# Scheme_alt.net
KiCad netlist of a schematic drawn in EAGLE
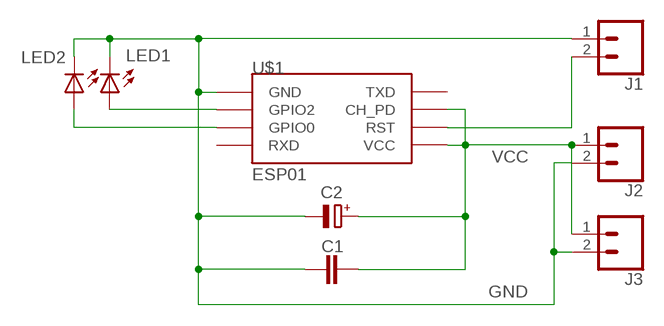
[diagram p0: schematic, sheet 1]

(export (version "E")
  (design (tool "Eeschema 10.0.6"))
  (components
    (comp (ref "C1")
      (value "C-EU025-024X044")
      (footprint "eagle-import:C025-024X044")
      (libsource (lib "eagle-import") (part "C-EU025-024X044"))
    )
    (comp (ref "C2")
      (value "CPOL-EUE5-10.5")
      (footprint "eagle-import:E5-10,5")
      (libsource (lib "eagle-import") (part "CPOL-EUE5-10.5"))
    )
    (comp (ref "J1")
      (value "CONN_02")
      (footprint "eagle-import:1X02")
      (libsource (lib "eagle-import") (part "CONN_02"))
    )
    (comp (ref "J2")
      (value "CONN_02")
      (footprint "eagle-import:1X02")
      (libsource (lib "eagle-import") (part "CONN_02"))
    )
    (comp (ref "J3")
      (value "CONN_02")
      (footprint "eagle-import:1X02")
      (libsource (lib "eagle-import") (part "CONN_02"))
    )
    (comp (ref "LED1")
      (value "LED3MM")
      (footprint "eagle-import:LED3MM")
      (libsource (lib "eagle-import") (part "LED3MM"))
    )
    (comp (ref "LED2")
      (value "LED3MM")
      (footprint "eagle-import:LED3MM")
      (libsource (lib "eagle-import") (part "LED3MM"))
    )
    (comp (ref "U$1")
      (value "ESP01")
      (footprint "eagle-import:ESP01")
      (libsource (lib "eagle-import") (part "ESP01"))
    )
  )
  (nets
    (net (code "1") (name "/GND") (class "Default")
      (node (ref "C1") (pin "2") (pinfunction "2_2") (pintype "passive"))
      (node (ref "C2") (pin "-") (pinfunction "-_-") (pintype "passive"))
      (node (ref "J1") (pin "1") (pinfunction "1_1") (pintype "passive"))
      (node (ref "J2") (pin "2") (pinfunction "2_2") (pintype "passive"))
      (node (ref "J3") (pin "2") (pinfunction "2_2") (pintype "passive"))
      (node (ref "LED1") (pin "K") (pinfunction "C_K") (pintype "passive"))
      (node (ref "LED2") (pin "K") (pinfunction "C_K") (pintype "passive"))
      (node (ref "U$1") (pin "GND") (pinfunction "GND_GND") (pintype "bidirectional"))
    )
    (net (code "2") (name "/VCC") (class "Default")
      (node (ref "C1") (pin "1") (pinfunction "1_1") (pintype "passive"))
      (node (ref "C2") (pin "+") (pinfunction "+_+") (pintype "passive"))
      (node (ref "J2") (pin "1") (pinfunction "1_1") (pintype "passive"))
      (node (ref "J3") (pin "1") (pinfunction "1_1") (pintype "passive"))
      (node (ref "U$1") (pin "CH_PD") (pinfunction "CH_PD_CH_PD") (pintype "bidirectional"))
      (node (ref "U$1") (pin "VCC") (pinfunction "VCC_VCC") (pintype "bidirectional"))
    )
    (net (code "3") (name "Net-(J1-Pad2)") (class "Default")
      (node (ref "J1") (pin "2") (pinfunction "2_2") (pintype "passive"))
      (node (ref "U$1") (pin "RST") (pinfunction "RST_RST") (pintype "bidirectional"))
    )
    (net (code "4") (name "Net-(LED1-PadA)") (class "Default")
      (node (ref "LED1") (pin "A") (pinfunction "A_A") (pintype "passive"))
      (node (ref "U$1") (pin "GPIO2") (pinfunction "GPIO2_GPIO2") (pintype "bidirectional"))
    )
    (net (code "5") (name "Net-(LED2-PadA)") (class "Default")
      (node (ref "LED2") (pin "A") (pinfunction "A_A") (pintype "passive"))
      (node (ref "U$1") (pin "GPIO0") (pinfunction "GPIO0_GPIO0") (pintype "bidirectional"))
    )
    (net (code "6") (name "unconnected-(U$1-RXD-PadRX)") (class "Default")
      (node (ref "U$1") (pin "RX") (pinfunction "RXD_RX") (pintype "bidirectional"))
    )
    (net (code "7") (name "unconnected-(U$1-TXD-PadTX)") (class "Default")
      (node (ref "U$1") (pin "TX") (pinfunction "TXD_TX") (pintype "bidirectional"))
    )
  )
)
